# 03-LED-GREEN.net
KiCad netlist of a schematic drawn in Altium Designer
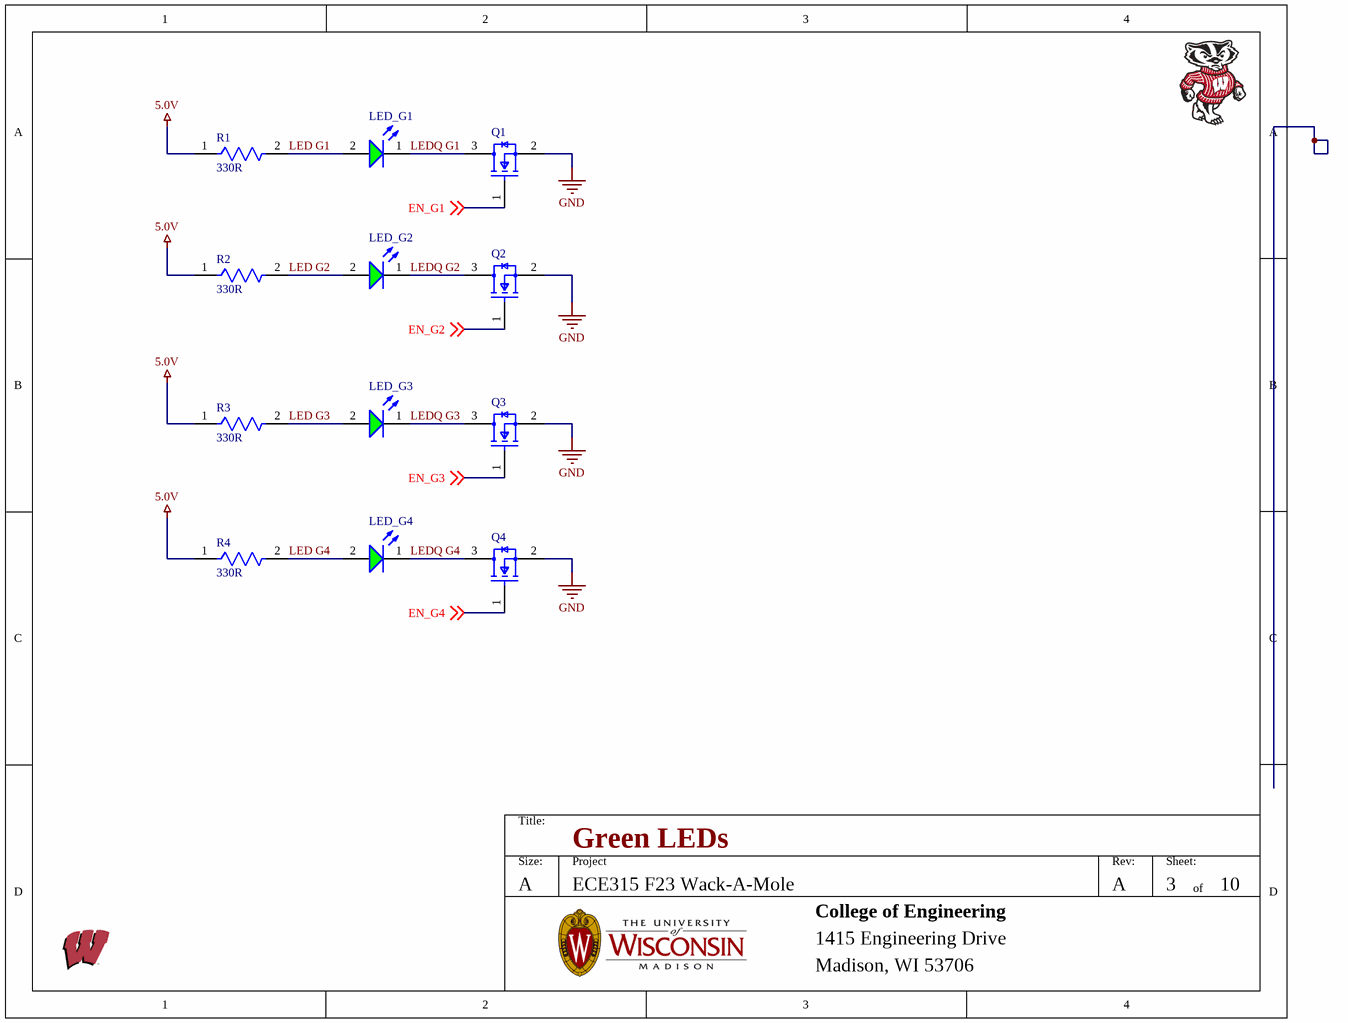
[diagram p0: 03-LED-GREEN.SchDoc]

(export (version "E")
  (design (tool "Eeschema 10.0.6"))
  (components
    (comp (ref "LED_G1")
      (value "150120GS75000")
      (footprint "WL-SMCW_1206_150120xx75000")
      (fields (field (name "MANUFACTURER") "Wurth Electronics"))
      (libsource (lib "Altium Content Vault") (part "LED_Green_2A-1K"))
    )
    (comp (ref "LED_G2")
      (value "150120GS75000")
      (footprint "WL-SMCW_1206_150120xx75000")
      (fields (field (name "MANUFACTURER") "Wurth Electronics"))
      (libsource (lib "Altium Content Vault") (part "LED_Green_2A-1K"))
    )
    (comp (ref "LED_G3")
      (value "150120GS75000")
      (footprint "WL-SMCW_1206_150120xx75000")
      (fields (field (name "MANUFACTURER") "Wurth Electronics"))
      (libsource (lib "Altium Content Vault") (part "LED_Green_2A-1K"))
    )
    (comp (ref "LED_G4")
      (value "150120GS75000")
      (footprint "WL-SMCW_1206_150120xx75000")
      (fields (field (name "MANUFACTURER") "Wurth Electronics"))
      (libsource (lib "Altium Content Vault") (part "LED_Green_2A-1K"))
    )
    (comp (ref "Q1")
      (value "2N7002-7-F")
      (footprint "FP-SOT23-MFG")
      (description "MOSFET N-CH 60V 115MA SOT23-3")
      (fields (field (name "VOLTAGE") "60V"))
      (libsource (lib "Altium Content Vault") (part "3b9c635fedb024a5347a57b145af9cc"))
    )
    (comp (ref "Q2")
      (value "2N7002-7-F")
      (footprint "FP-SOT23-MFG")
      (description "MOSFET N-CH 60V 115MA SOT23-3")
      (fields (field (name "VOLTAGE") "60V"))
      (libsource (lib "Altium Content Vault") (part "3b9c635fedb024a5347a57b145af9cc"))
    )
    (comp (ref "Q3")
      (value "2N7002-7-F")
      (footprint "FP-SOT23-MFG")
      (description "MOSFET N-CH 60V 115MA SOT23-3")
      (fields (field (name "VOLTAGE") "60V"))
      (libsource (lib "Altium Content Vault") (part "3b9c635fedb024a5347a57b145af9cc"))
    )
    (comp (ref "Q4")
      (value "2N7002-7-F")
      (footprint "FP-SOT23-MFG")
      (description "MOSFET N-CH 60V 115MA SOT23-3")
      (fields (field (name "VOLTAGE") "60V"))
      (libsource (lib "Altium Content Vault") (part "3b9c635fedb024a5347a57b145af9cc"))
    )
    (comp (ref "R1")
      (value "CRCW1206330RFKEA")
      (footprint "FP-CRCW1206-e3-IPC_A")
      (description "RES Thick Film, 330Ω, 1%, 0.25W, 100ppm/°C, 1206")
      (fields (field (name "TOLERANCE") "1%") (field (name "RESISTANCE") "330R"))
      (libsource (lib "Altium Content Vault") (part "1029c3af85768c4190bb7ad29bc67b5"))
    )
    (comp (ref "R2")
      (value "CRCW1206330RFKEA")
      (footprint "FP-CRCW1206-e3-IPC_A")
      (description "RES Thick Film, 330Ω, 1%, 0.25W, 100ppm/°C, 1206")
      (fields (field (name "TOLERANCE") "1%") (field (name "RESISTANCE") "330R"))
      (libsource (lib "Altium Content Vault") (part "1029c3af85768c4190bb7ad29bc67b5"))
    )
    (comp (ref "R3")
      (value "CRCW1206330RFKEA")
      (footprint "FP-CRCW1206-e3-IPC_A")
      (description "RES Thick Film, 330Ω, 1%, 0.25W, 100ppm/°C, 1206")
      (fields (field (name "TOLERANCE") "1%") (field (name "RESISTANCE") "330R"))
      (libsource (lib "Altium Content Vault") (part "1029c3af85768c4190bb7ad29bc67b5"))
    )
    (comp (ref "R4")
      (value "CRCW1206330RFKEA")
      (footprint "FP-CRCW1206-e3-IPC_A")
      (description "RES Thick Film, 330Ω, 1%, 0.25W, 100ppm/°C, 1206")
      (fields (field (name "TOLERANCE") "1%") (field (name "RESISTANCE") "330R"))
      (libsource (lib "Altium Content Vault") (part "1029c3af85768c4190bb7ad29bc67b5"))
    )
  )
  (nets
    (net (code "1") (name "/LED G1") (class "Default")
      (node (ref "LED_G1") (pin "2") (pinfunction "A_2") (pintype "passive"))
      (node (ref "R1") (pin "2") (pinfunction "2_2") (pintype "passive"))
    )
    (net (code "2") (name "/LED G2") (class "Default")
      (node (ref "LED_G2") (pin "2") (pinfunction "A_2") (pintype "passive"))
      (node (ref "R2") (pin "2") (pinfunction "2_2") (pintype "passive"))
    )
    (net (code "3") (name "/LED G3") (class "Default")
      (node (ref "LED_G3") (pin "2") (pinfunction "A_2") (pintype "passive"))
      (node (ref "R3") (pin "2") (pinfunction "2_2") (pintype "passive"))
    )
    (net (code "4") (name "/LED G4") (class "Default")
      (node (ref "LED_G4") (pin "2") (pinfunction "A_2") (pintype "passive"))
      (node (ref "R4") (pin "2") (pinfunction "2_2") (pintype "passive"))
    )
    (net (code "5") (name "/LEDQ G1") (class "Default")
      (node (ref "LED_G1") (pin "1") (pinfunction "K_1") (pintype "passive"))
      (node (ref "Q1") (pin "3") (pinfunction "D_3") (pintype "passive"))
    )
    (net (code "6") (name "/LEDQ G2") (class "Default")
      (node (ref "LED_G2") (pin "1") (pinfunction "K_1") (pintype "passive"))
      (node (ref "Q2") (pin "3") (pinfunction "D_3") (pintype "passive"))
    )
    (net (code "7") (name "/LEDQ G3") (class "Default")
      (node (ref "LED_G3") (pin "1") (pinfunction "K_1") (pintype "passive"))
      (node (ref "Q3") (pin "3") (pinfunction "D_3") (pintype "passive"))
    )
    (net (code "8") (name "/LEDQ G4") (class "Default")
      (node (ref "LED_G4") (pin "1") (pinfunction "K_1") (pintype "passive"))
      (node (ref "Q4") (pin "3") (pinfunction "D_3") (pintype "passive"))
    )
    (net (code "9") (name "5.0V") (class "Default")
      (node (ref "R1") (pin "1") (pinfunction "1_1") (pintype "passive"))
      (node (ref "R2") (pin "1") (pinfunction "1_1") (pintype "passive"))
      (node (ref "R3") (pin "1") (pinfunction "1_1") (pintype "passive"))
      (node (ref "R4") (pin "1") (pinfunction "1_1") (pintype "passive"))
    )
    (net (code "10") (name "EN_G1") (class "Default")
      (node (ref "Q1") (pin "1") (pinfunction "G_1") (pintype "passive"))
    )
    (net (code "11") (name "EN_G2") (class "Default")
      (node (ref "Q2") (pin "1") (pinfunction "G_1") (pintype "passive"))
    )
    (net (code "12") (name "EN_G3") (class "Default")
      (node (ref "Q3") (pin "1") (pinfunction "G_1") (pintype "passive"))
    )
    (net (code "13") (name "EN_G4") (class "Default")
      (node (ref "Q4") (pin "1") (pinfunction "G_1") (pintype "passive"))
    )
    (net (code "14") (name "GND") (class "Default")
      (node (ref "Q1") (pin "2") (pinfunction "S_2") (pintype "passive"))
      (node (ref "Q2") (pin "2") (pinfunction "S_2") (pintype "passive"))
      (node (ref "Q3") (pin "2") (pinfunction "S_2") (pintype "passive"))
      (node (ref "Q4") (pin "2") (pinfunction "S_2") (pintype "passive"))
    )
  )
)
